# Schematic_EasyEDA_Half_Cat_GSE_Controlle.net
KiCad netlist of a schematic drawn in EasyEDA
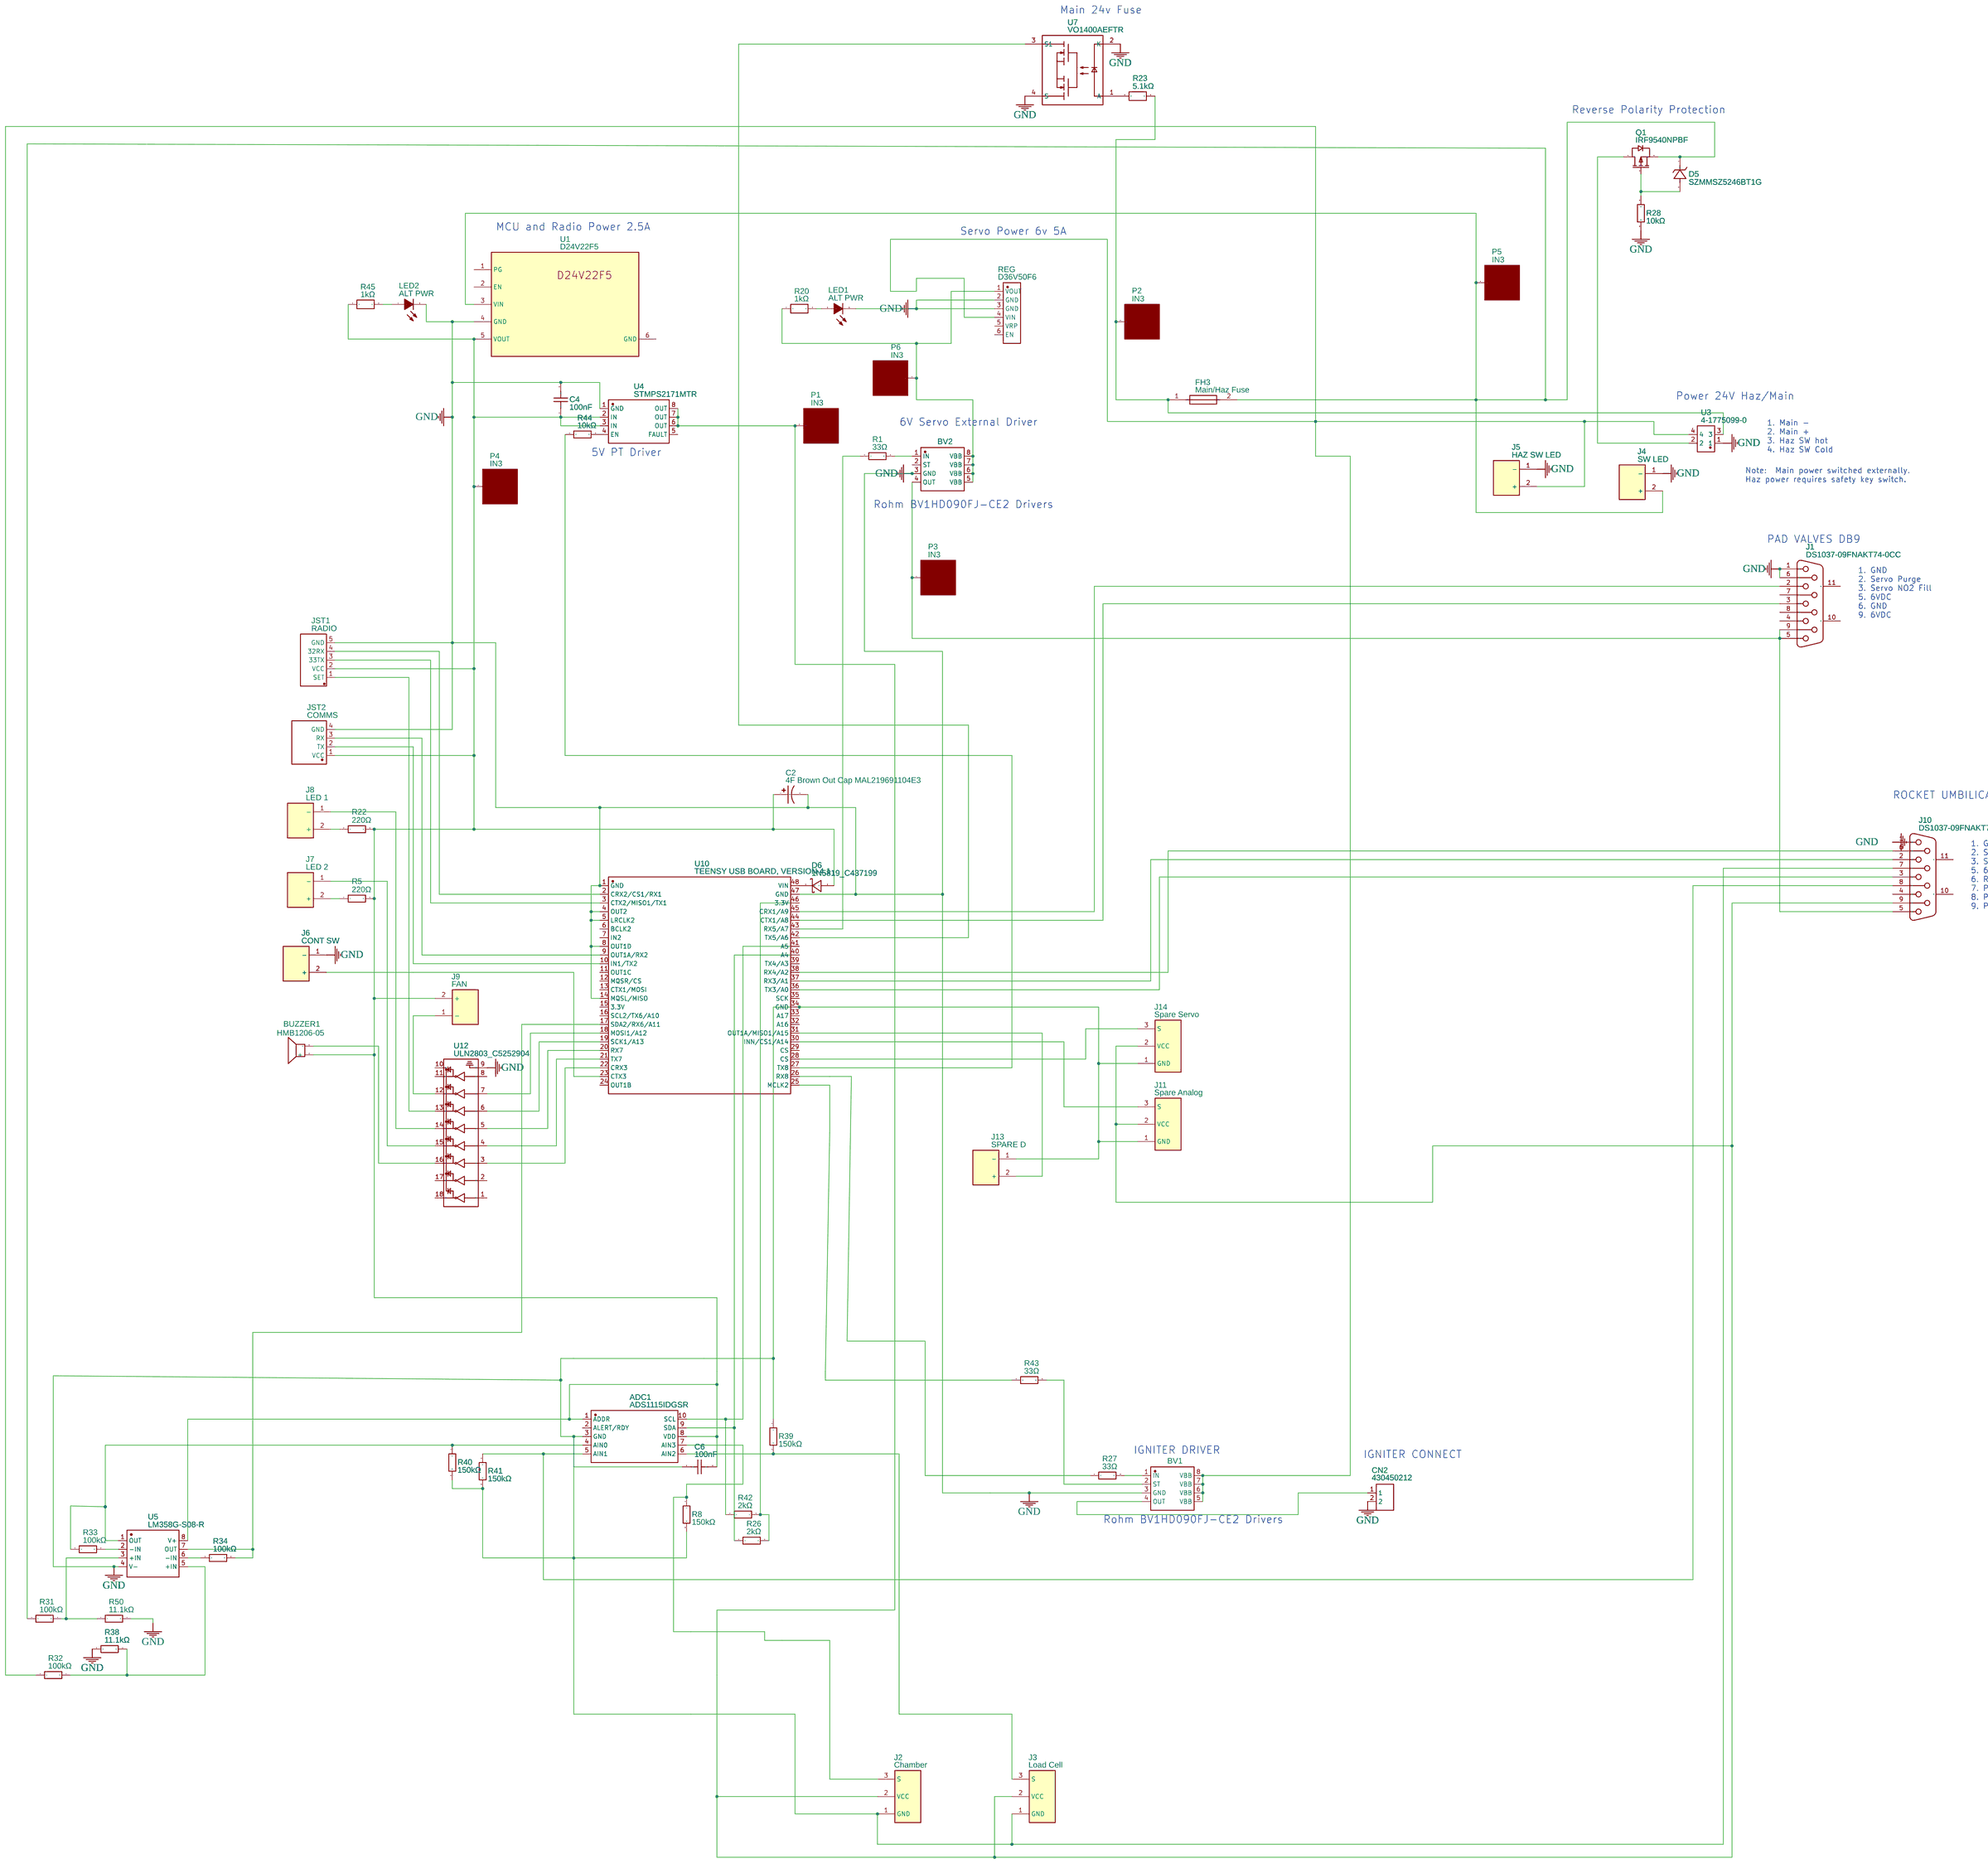
[diagram p0: schematic sheet]

(export (version "E")
  (design (tool "Eeschema 10.0.6"))
  (components
    (comp (ref "ADC1")
      (value "ADS1115IDGSR")
      (fields (field (name "Manufacturer") "TI(德州仪器)"))
      (libsource (lib "") (part "ADS1115IDGSR"))
    )
    (comp (ref "BUZZER1")
      (value "HMB1206-05")
      (fields (field (name "Manufacturer") "HNDZ"))
      (libsource (lib "") (part "HMB1206-05"))
    )
    (comp (ref "BV1")
      (value "BV2")
      (fields (field (name "Manufacturer Part") "BV1HD090FJ-CE2") (field (name "Manufacturer") "ROHM(罗姆)"))
      (libsource (lib "") (part "BV1HD090FJ-CE2"))
    )
    (comp (ref "BV2")
      (value "BV1")
      (fields (field (name "Manufacturer Part") "BV1HD090FJ-CE2") (field (name "Manufacturer") "ROHM(罗姆)"))
      (libsource (lib "") (part "BV1HD090FJ-CE2"))
    )
    (comp (ref "C2") (value "4F Brown Out Cap MAL219691104E3") (libsource (lib "") (part "C_Tan_SMD_A_US")))
    (comp (ref "C4")
      (value "100nF")
      (fields
        (field (name "Manufacturer Part") "GRM155B31C104KA87D")
        (field (name "Manufacturer") "muRata(村田)")
      )
      (libsource (lib "") (part "GRM155B31C104KA87D"))
    )
    (comp (ref "C6")
      (value "100nF")
      (fields
        (field (name "Manufacturer Part") "GRM155B31C104KA87D")
        (field (name "Manufacturer") "muRata(村田)")
      )
      (libsource (lib "") (part "GRM155B31C104KA87D_1"))
    )
    (comp (ref "CN2")
      (value "430450212")
      (fields (field (name "Manufacturer") "MOLEX"))
      (libsource (lib "") (part "430450212"))
    )
    (comp (ref "D5")
      (value "SZMMSZ5246BT1G")
      (fields (field (name "Manufacturer") "onsemi(安森美)"))
      (libsource (lib "") (part "SZMMSZ5246BT1G"))
    )
    (comp (ref "D6")
      (value "1N5819_C437199")
      (fields (field (name "Manufacturer Part") "1N5819") (field (name "Manufacturer") "KEXIN(科信)"))
      (libsource (lib "") (part "1N5819_C437199"))
    )
    (comp (ref "FH3")
      (value "Main/Haz Fuse")
      (fields (field (name "Manufacturer Part") "01000063Z") (field (name "Manufacturer") "Littlefuse"))
      (libsource (lib "") (part "Mini Blade Fuse Holder"))
    )
    (comp (ref "J1")
      (value "DS1037-09FNAKT74-0CC")
      (fields (field (name "Manufacturer") "CONNFLY"))
      (libsource (lib "") (part "DS1037-09FNAKT74-0CC"))
    )
    (comp (ref "J2")
      (value "Chamber")
      (fields (field (name "Manufacturer Part") "B3B-PH-K-S(LF)(SN)") (field (name "Manufacturer") "JST"))
      (libsource (lib "") (part "Unknown_155_680"))
    )
    (comp (ref "J3")
      (value "Load Cell")
      (fields (field (name "Manufacturer Part") "B3B-PH-K-S(LF)(SN)") (field (name "Manufacturer") "JST"))
      (libsource (lib "") (part "Unknown_310_680"))
    )
    (comp (ref "J4")
      (value "SW LED")
      (fields (field (name "Manufacturer Part") "B2B-PH-K-S(LF)(SN)") (field (name "Manufacturer") "JST"))
      (libsource (lib "") (part "B2B-PH-K-S(LF)(SN)"))
    )
    (comp (ref "J5")
      (value "HAZ SW LED")
      (fields (field (name "Manufacturer Part") "B2B-PH-K-S(LF)(SN)") (field (name "Manufacturer") "JST"))
      (libsource (lib "") (part "B2B-PH-K-S(LF)(SN)"))
    )
    (comp (ref "J6")
      (value "CONT SW")
      (fields (field (name "Manufacturer Part") "B2B-PH-K-S(LF)(SN)") (field (name "Manufacturer") "JST"))
      (libsource (lib "") (part "B2B-PH-K-S(LF)(SN)"))
    )
    (comp (ref "J7")
      (value "LED 2")
      (fields (field (name "Manufacturer Part") "B2B-PH-K-S(LF)(SN)") (field (name "Manufacturer") "JST"))
      (libsource (lib "") (part "B2B-PH-K-S(LF)(SN)"))
    )
    (comp (ref "J8")
      (value "LED 1")
      (fields (field (name "Manufacturer Part") "B2B-PH-K-S(LF)(SN)") (field (name "Manufacturer") "JST"))
      (libsource (lib "") (part "B2B-PH-K-S(LF)(SN)"))
    )
    (comp (ref "J9")
      (value "FAN")
      (fields (field (name "Manufacturer Part") "B2B-PH-K-S(LF)(SN)") (field (name "Manufacturer") "JST"))
      (libsource (lib "") (part "B2B-PH-K-S(LF)(SN)_1"))
    )
    (comp (ref "J10")
      (value "DS1037-09FNAKT74-0CC")
      (fields (field (name "Manufacturer") "CONNFLY"))
      (libsource (lib "") (part "DS1037-09FNAKT74-0CC"))
    )
    (comp (ref "J11")
      (value "Spare Analog")
      (fields (field (name "Manufacturer Part") "B3B-PH-K-S(LF)(SN)") (field (name "Manufacturer") "JST"))
      (libsource (lib "") (part "Unknown_455_-95"))
    )
    (comp (ref "J13")
      (value "SPARE D")
      (fields (field (name "Manufacturer Part") "B2B-PH-K-S(LF)(SN)") (field (name "Manufacturer") "JST"))
      (libsource (lib "") (part "B2B-PH-K-S(LF)(SN)"))
    )
    (comp (ref "J14")
      (value "Spare Servo")
      (fields (field (name "Manufacturer Part") "B3B-PH-K-S(LF)(SN)") (field (name "Manufacturer") "JST"))
      (libsource (lib "") (part "Unknown_455_-185"))
    )
    (comp (ref "JST1")
      (value "RADIO")
      (fields (field (name "Manufacturer Part") "B5B-PH-K-S(LF)(SN)") (field (name "Manufacturer") "JST"))
      (libsource (lib "") (part "B5B-PH-K-S-(LF)(SN)"))
    )
    (comp (ref "JST2")
      (value "COMMS")
      (fields (field (name "Manufacturer Part") "B4B-PH-K(LF)(SN)") (field (name "Manufacturer") "JST"))
      (libsource (lib "") (part "B4B-PH-K(LF)(SN)"))
    )
    (comp (ref "LED1")
      (value "ALT PWR")
      (fields
        (field (name "Manufacturer Part") "67-21/R6C-FN2Q1BZ/2T")
        (field (name "Manufacturer") "EVERLIGHT")
      )
      (libsource (lib "") (part "67-21/R6C-FN2Q1BZ/2T"))
    )
    (comp (ref "LED2")
      (value "ALT PWR")
      (fields
        (field (name "Manufacturer Part") "67-21/R6C-FN2Q1BZ/2T")
        (field (name "Manufacturer") "EVERLIGHT")
      )
      (libsource (lib "") (part "67-21/R6C-FN2Q1BZ/2T"))
    )
    (comp (ref "P1")
      (value "IN3")
      (fields (field (name "Manufacturer Part") "Soldering pad"))
      (libsource (lib "") (part "Solder Pad"))
    )
    (comp (ref "P2")
      (value "IN3")
      (fields (field (name "Manufacturer Part") "Soldering pad"))
      (libsource (lib "") (part "Solder Pad"))
    )
    (comp (ref "P3")
      (value "IN3")
      (fields (field (name "Manufacturer Part") "Soldering pad"))
      (libsource (lib "") (part "Solder Pad"))
    )
    (comp (ref "P4")
      (value "IN3")
      (fields (field (name "Manufacturer Part") "Soldering pad"))
      (libsource (lib "") (part "Solder Pad"))
    )
    (comp (ref "P5")
      (value "IN3")
      (fields (field (name "Manufacturer Part") "Soldering pad"))
      (libsource (lib "") (part "Solder Pad"))
    )
    (comp (ref "P6")
      (value "IN3")
      (fields (field (name "Manufacturer Part") "Soldering pad"))
      (libsource (lib "") (part "Solder Pad_1"))
    )
    (comp (ref "Q1")
      (value "IRF9540NPBF")
      (fields (field (name "Manufacturer") "Infineon(英飞凌)"))
      (libsource (lib "") (part "IRF9540NPBF"))
    )
    (comp (ref "R1")
      (value "33Ω")
      (fields (field (name "Manufacturer Part") "RM06FTN33R0") (field (name "Manufacturer") "大毅科技"))
      (libsource (lib "") (part "RM06FTN33R0"))
    )
    (comp (ref "R5")
      (value "220Ω")
      (fields (field (name "Manufacturer Part") "MCWR08X221 JTL") (field (name "Manufacturer") "Multicomp"))
      (libsource (lib "") (part "MCWR08X221-JTL"))
    )
    (comp (ref "R8")
      (value "150kΩ")
      (fields (field (name "Manufacturer Part") "RK73B2ATTD154J") (field (name "Manufacturer") "KOA"))
      (libsource (lib "") (part "RK73B2ATTD154J"))
    )
    (comp (ref "R20")
      (value "1kΩ")
      (fields
        (field (name "Manufacturer Part") "TC0550F1001T5J")
        (field (name "Manufacturer") "UNI-ROYAL(厚声)")
      )
      (libsource (lib "") (part "TC0550F1001T5J"))
    )
    (comp (ref "R22")
      (value "220Ω")
      (fields (field (name "Manufacturer Part") "MCWR08X221 JTL") (field (name "Manufacturer") "Multicomp"))
      (libsource (lib "") (part "MCWR08X221-JTL"))
    )
    (comp (ref "R23")
      (value "5.1kΩ")
      (fields (field (name "Manufacturer Part") "SCR0805F5K1") (field (name "Manufacturer") "VO(翔胜)"))
      (libsource (lib "") (part "SCR0805F5K1"))
    )
    (comp (ref "R26")
      (value "2kΩ")
      (fields (field (name "Manufacturer Part") "RC0805DR-072KL") (field (name "Manufacturer") "YAGEO(国巨)"))
      (libsource (lib "") (part "RC0805DR-072KL"))
    )
    (comp (ref "R27")
      (value "33Ω")
      (fields (field (name "Manufacturer Part") "RM06FTN33R0") (field (name "Manufacturer") "大毅科技"))
      (libsource (lib "") (part "RM06FTN33R0"))
    )
    (comp (ref "R28")
      (value "10kΩ")
      (fields (field (name "Manufacturer Part") "HPCR0805F10K0K9") (field (name "Manufacturer") "RESI(开步睿思)"))
      (libsource (lib "") (part "HPCR0805F10K0K9_1"))
    )
    (comp (ref "R31")
      (value "100kΩ")
      (fields (field (name "Manufacturer Part") "RM10JTN104") (field (name "Manufacturer") "大毅科技"))
      (libsource (lib "") (part "RM10JTN104"))
    )
    (comp (ref "R32")
      (value "100kΩ")
      (fields (field (name "Manufacturer Part") "RM10JTN104") (field (name "Manufacturer") "大毅科技"))
      (libsource (lib "") (part "RM10JTN104"))
    )
    (comp (ref "R33")
      (value "100kΩ")
      (fields (field (name "Manufacturer Part") "RM10JTN104") (field (name "Manufacturer") "大毅科技"))
      (libsource (lib "") (part "RM10JTN104"))
    )
    (comp (ref "R34")
      (value "100kΩ")
      (fields (field (name "Manufacturer Part") "RM10JTN104") (field (name "Manufacturer") "大毅科技"))
      (libsource (lib "") (part "RM10JTN104"))
    )
    (comp (ref "R38")
      (value "11.1kΩ")
      (fields (field (name "Manufacturer Part") "RT0603BRD0711K1L") (field (name "Manufacturer") "YAGEO(国巨)"))
      (libsource (lib "") (part "RT0603BRD0711K1L"))
    )
    (comp (ref "R39")
      (value "150kΩ")
      (fields (field (name "Manufacturer Part") "RK73B2ATTD154J") (field (name "Manufacturer") "KOA"))
      (libsource (lib "") (part "RK73B2ATTD154J"))
    )
    (comp (ref "R40")
      (value "150kΩ")
      (fields (field (name "Manufacturer Part") "RK73B2ATTD154J") (field (name "Manufacturer") "KOA"))
      (libsource (lib "") (part "RK73B2ATTD154J"))
    )
    (comp (ref "R41")
      (value "150kΩ")
      (fields (field (name "Manufacturer Part") "RK73B2ATTD154J") (field (name "Manufacturer") "KOA"))
      (libsource (lib "") (part "RK73B2ATTD154J"))
    )
    (comp (ref "R42")
      (value "2kΩ")
      (fields (field (name "Manufacturer Part") "RC0805DR-072KL") (field (name "Manufacturer") "YAGEO(国巨)"))
      (libsource (lib "") (part "RC0805DR-072KL"))
    )
    (comp (ref "R43")
      (value "33Ω")
      (fields (field (name "Manufacturer Part") "RM06FTN33R0") (field (name "Manufacturer") "大毅科技"))
      (libsource (lib "") (part "RM06FTN33R0"))
    )
    (comp (ref "R44")
      (value "10kΩ")
      (fields (field (name "Manufacturer Part") "HPCR0805F10K0K9") (field (name "Manufacturer") "RESI(开步睿思)"))
      (libsource (lib "") (part "HPCR0805F10K0K9"))
    )
    (comp (ref "R45")
      (value "1kΩ")
      (fields
        (field (name "Manufacturer Part") "TC0550F1001T5J")
        (field (name "Manufacturer") "UNI-ROYAL(厚声)")
      )
      (libsource (lib "") (part "TC0550F1001T5J"))
    )
    (comp (ref "R50")
      (value "11.1kΩ")
      (fields (field (name "Manufacturer Part") "RT0603BRD0711K1L") (field (name "Manufacturer") "YAGEO(国巨)"))
      (libsource (lib "") (part "RT0603BRD0711K1L"))
    )
    (comp (ref "REG") (value "D36V50F6") (libsource (lib "") (part "D36V50F6")))
    (comp (ref "U1") (value "D24V22F5") (libsource (lib "") (part "D24V22F5")))
    (comp (ref "U3")
      (value "4-1775099-0")
      (fields (field (name "Manufacturer") "TE Connectivity(美国泰科)"))
      (libsource (lib "") (part "4-1775099-0"))
    )
    (comp (ref "U4")
      (value "STMPS2171MTR")
      (fields (field (name "Manufacturer") "ST(意法半导体)"))
      (libsource (lib "") (part "STMPS2171MTR"))
    )
    (comp (ref "U5")
      (value "LM358G-S08-R")
      (fields (field (name "Manufacturer") "UTC"))
      (libsource (lib "") (part "LM358G-S08-R"))
    )
    (comp (ref "U7")
      (value "VO1400AEFTR")
      (fields (field (name "Manufacturer") "VISHAY(威世)"))
      (libsource (lib "") (part "VO1400AEFTR"))
    )
    (comp (ref "U10")
      (value "TEENSY USB BOARD, VERSION 4.1")
      (fields (field (name "Manufacturer Part") "Teensy USB Board, Version 4.1"))
      (libsource (lib "") (part "TEENSY USB BOARD, VERSION 4.1"))
    )
    (comp (ref "U12")
      (value "ULN2803_C5252904")
      (fields (field (name "Manufacturer Part") "ULN2803") (field (name "Manufacturer") "MSKSEMI(美森科)"))
      (libsource (lib "") (part "ULN2803_C5252904"))
    )
  )
  (nets
    (net (code "1") (name "GND") (class "Default")
      (node (ref "ADC1") (pin "3") (pinfunction "GND_3") (pintype "unspecified"))
      (node (ref "BV1") (pin "3") (pinfunction "GND_3") (pintype "unspecified"))
      (node (ref "BV2") (pin "3") (pinfunction "GND_3") (pintype "unspecified"))
      (node (ref "C2") (pin "2") (pinfunction "2_2") (pintype "unspecified"))
      (node (ref "C4") (pin "2") (pinfunction "2_2") (pintype "unspecified"))
      (node (ref "C6") (pin "1") (pinfunction "1_1") (pintype "unspecified"))
      (node (ref "CN2") (pin "2") (pinfunction "2_2") (pintype "unspecified"))
      (node (ref "J1") (pin "1") (pinfunction "1_1") (pintype "input"))
      (node (ref "J1") (pin "6") (pinfunction "6_6") (pintype "input"))
      (node (ref "J10") (pin "1") (pinfunction "1_1") (pintype "input"))
      (node (ref "J10") (pin "7") (pinfunction "7_7") (pintype "input"))
      (node (ref "J11") (pin "1") (pinfunction "GND_1") (pintype "input"))
      (node (ref "J13") (pin "1") (pinfunction "-_1") (pintype "input"))
      (node (ref "J14") (pin "1") (pinfunction "GND_1") (pintype "input"))
      (node (ref "J2") (pin "1") (pinfunction "GND_1") (pintype "input"))
      (node (ref "J3") (pin "1") (pinfunction "GND_1") (pintype "input"))
      (node (ref "J4") (pin "1") (pinfunction "-_1") (pintype "input"))
      (node (ref "J5") (pin "1") (pinfunction "-_1") (pintype "input"))
      (node (ref "J6") (pin "1") (pinfunction "-_1") (pintype "input"))
      (node (ref "JST1") (pin "5") (pinfunction "GND_5") (pintype "unspecified"))
      (node (ref "JST2") (pin "4") (pinfunction "GND_4") (pintype "unspecified"))
      (node (ref "LED1") (pin "2") (pinfunction "C_2") (pintype "input"))
      (node (ref "LED2") (pin "2") (pinfunction "C_2") (pintype "input"))
      (node (ref "R28") (pin "2") (pinfunction "2_2") (pintype "unspecified"))
      (node (ref "R38") (pin "1") (pinfunction "1_1") (pintype "unspecified"))
      (node (ref "R39") (pin "1") (pinfunction "1_1") (pintype "unspecified"))
      (node (ref "R40") (pin "2") (pinfunction "2_2") (pintype "unspecified"))
      (node (ref "R41") (pin "2") (pinfunction "2_2") (pintype "unspecified"))
      (node (ref "R50") (pin "2") (pinfunction "2_2") (pintype "unspecified"))
      (node (ref "R8") (pin "2") (pinfunction "2_2") (pintype "unspecified"))
      (node (ref "REG") (pin "2") (pinfunction "GND_2") (pintype "unspecified"))
      (node (ref "REG") (pin "3") (pinfunction "GND_3") (pintype "unspecified"))
      (node (ref "U1") (pin "4") (pinfunction "GND_4") (pintype "unspecified"))
      (node (ref "U10") (pin "1") (pinfunction "GND_1") (pintype "unspecified"))
      (node (ref "U10") (pin "14") (pinfunction "MQSL/MISO_14") (pintype "unspecified"))
      (node (ref "U10") (pin "34") (pinfunction "GND_34") (pintype "unspecified"))
      (node (ref "U10") (pin "4") (pinfunction "OUT2_4") (pintype "unspecified"))
      (node (ref "U10") (pin "47") (pinfunction "GND_47") (pintype "unspecified"))
      (node (ref "U10") (pin "5") (pinfunction "LRCLK2_5") (pintype "unspecified"))
      (node (ref "U10") (pin "8") (pinfunction "OUT1D_8") (pintype "unspecified"))
      (node (ref "U12") (pin "9") (pinfunction "GND_9") (pintype "unspecified"))
      (node (ref "U3") (pin "1") (pinfunction "1_1") (pintype "unspecified"))
      (node (ref "U4") (pin "1") (pinfunction "GND_1") (pintype "unspecified"))
      (node (ref "U5") (pin "4") (pinfunction "V-_4") (pintype "unspecified"))
      (node (ref "U7") (pin "2") (pinfunction "K_2") (pintype "unspecified"))
      (node (ref "U7") (pin "4") (pinfunction "S_4") (pintype "unspecified"))
    )
    (net (code "2") (name "Net-(ADC1-ADDR)") (class "Default")
      (node (ref "ADC1") (pin "1") (pinfunction "ADDR_1") (pintype "unspecified"))
      (node (ref "ADC1") (pin "8") (pinfunction "VDD_8") (pintype "unspecified"))
      (node (ref "BUZZER1") (pin "1") (pinfunction "+_1") (pintype "unspecified"))
      (node (ref "C2") (pin "1") (pinfunction "1_1") (pintype "unspecified"))
      (node (ref "C4") (pin "1") (pinfunction "1_1") (pintype "unspecified"))
      (node (ref "C6") (pin "2") (pinfunction "2_2") (pintype "unspecified"))
      (node (ref "D6") (pin "2") (pinfunction "A_2") (pintype "unspecified"))
      (node (ref "J9") (pin "2") (pinfunction "+_2") (pintype "input"))
      (node (ref "JST1") (pin "2") (pinfunction "VCC_2") (pintype "unspecified"))
      (node (ref "JST2") (pin "1") (pinfunction "VCC_1") (pintype "unspecified"))
      (node (ref "P4") (pin "1") (pinfunction "1_1") (pintype "unspecified"))
      (node (ref "R22") (pin "2") (pinfunction "2_2") (pintype "unspecified"))
      (node (ref "R45") (pin "1") (pinfunction "1_1") (pintype "unspecified"))
      (node (ref "R5") (pin "2") (pinfunction "2_2") (pintype "unspecified"))
      (node (ref "U1") (pin "5") (pinfunction "VOUT_5") (pintype "unspecified"))
      (node (ref "U4") (pin "2") (pinfunction "IN_2") (pintype "unspecified"))
      (node (ref "U4") (pin "3") (pinfunction "IN_3") (pintype "unspecified"))
      (node (ref "U5") (pin "8") (pinfunction "V+_8") (pintype "unspecified"))
    )
    (net (code "3") (name "Net-(ADC1-AIN0)") (class "Default")
      (node (ref "ADC1") (pin "4") (pinfunction "AIN0_4") (pintype "unspecified"))
      (node (ref "R33") (pin "1") (pinfunction "1_1") (pintype "input"))
      (node (ref "R40") (pin "1") (pinfunction "1_1") (pintype "unspecified"))
      (node (ref "U5") (pin "1") (pinfunction "OUT_1") (pintype "unspecified"))
    )
    (net (code "4") (name "Net-(ADC1-AIN1)") (class "Default")
      (node (ref "ADC1") (pin "5") (pinfunction "AIN1_5") (pintype "unspecified"))
      (node (ref "J10") (pin "8") (pinfunction "8_8") (pintype "input"))
      (node (ref "R41") (pin "1") (pinfunction "1_1") (pintype "unspecified"))
    )
    (net (code "5") (name "Net-(ADC1-AIN2)") (class "Default")
      (node (ref "ADC1") (pin "6") (pinfunction "AIN2_6") (pintype "unspecified"))
      (node (ref "J3") (pin "3") (pinfunction "S_3") (pintype "input"))
      (node (ref "R39") (pin "2") (pinfunction "2_2") (pintype "unspecified"))
    )
    (net (code "6") (name "Net-(ADC1-AIN3)") (class "Default")
      (node (ref "ADC1") (pin "7") (pinfunction "AIN3_7") (pintype "unspecified"))
      (node (ref "J2") (pin "3") (pinfunction "S_3") (pintype "input"))
      (node (ref "R8") (pin "1") (pinfunction "1_1") (pintype "unspecified"))
    )
    (net (code "7") (name "Net-(ADC1-SCL)") (class "Default")
      (node (ref "ADC1") (pin "10") (pinfunction "SCL_10") (pintype "unspecified"))
      (node (ref "R42") (pin "1") (pinfunction "1_1") (pintype "unspecified"))
      (node (ref "U10") (pin "41") (pinfunction "A5_41") (pintype "unspecified"))
    )
    (net (code "8") (name "Net-(ADC1-SDA)") (class "Default")
      (node (ref "ADC1") (pin "9") (pinfunction "SDA_9") (pintype "unspecified"))
      (node (ref "R26") (pin "1") (pinfunction "1_1") (pintype "unspecified"))
      (node (ref "U10") (pin "40") (pinfunction "A4_40") (pintype "unspecified"))
    )
    (net (code "9") (name "Net-(BV1-IN)") (class "Default")
      (node (ref "BV1") (pin "1") (pinfunction "IN_1") (pintype "unspecified"))
      (node (ref "R1") (pin "2") (pinfunction "2_2") (pintype "unspecified"))
    )
    (net (code "10") (name "Net-(BV1-OUT)") (class "Default")
      (node (ref "BV1") (pin "4") (pinfunction "OUT_4") (pintype "unspecified"))
      (node (ref "J1") (pin "5") (pinfunction "5_5") (pintype "input"))
      (node (ref "J1") (pin "9") (pinfunction "9_9") (pintype "input"))
      (node (ref "J10") (pin "5") (pinfunction "5_5") (pintype "input"))
      (node (ref "P3") (pin "1") (pinfunction "1_1") (pintype "unspecified"))
    )
    (net (code "11") (name "Net-(BV2-IN)") (class "Default")
      (node (ref "BV2") (pin "1") (pinfunction "IN_1") (pintype "unspecified"))
      (node (ref "R27") (pin "2") (pinfunction "2_2") (pintype "unspecified"))
    )
    (net (code "12") (name "Net-(BV2-OUT)") (class "Default")
      (node (ref "BV2") (pin "4") (pinfunction "OUT_4") (pintype "unspecified"))
      (node (ref "CN2") (pin "1") (pinfunction "1_1") (pintype "unspecified"))
    )
    (net (code "13") (name "Net-(BV2-ST)") (class "Default")
      (node (ref "BV2") (pin "2") (pinfunction "ST_2") (pintype "unspecified"))
      (node (ref "R43") (pin "2") (pinfunction "2_2") (pintype "unspecified"))
    )
    (net (code "14") (name "Net-(D5-A)") (class "Default")
      (node (ref "D5") (pin "2") (pinfunction "A_2") (pintype "unspecified"))
      (node (ref "Q1") (pin "1") (pinfunction "G_1") (pintype "unspecified"))
      (node (ref "R28") (pin "1") (pinfunction "1_1") (pintype "unspecified"))
    )
    (net (code "15") (name "Net-(D5-C)") (class "Default")
      (node (ref "D5") (pin "1") (pinfunction "C_1") (pintype "unspecified"))
      (node (ref "FH3") (pin "2") (pinfunction "2_2") (pintype "unspecified"))
      (node (ref "J4") (pin "2") (pinfunction "+_2") (pintype "input"))
      (node (ref "P5") (pin "1") (pinfunction "1_1") (pintype "unspecified"))
      (node (ref "Q1") (pin "3") (pinfunction "S_3") (pintype "unspecified"))
      (node (ref "R31") (pin "1") (pinfunction "1_1") (pintype "input"))
      (node (ref "U1") (pin "3") (pinfunction "VIN_3") (pintype "unspecified"))
    )
    (net (code "16") (name "Net-(D6-C)") (class "Default")
      (node (ref "D6") (pin "1") (pinfunction "C_1") (pintype "unspecified"))
      (node (ref "U10") (pin "48") (pinfunction "VIN_48") (pintype "unspecified"))
    )
    (net (code "17") (name "Net-(FH3-Pad1)") (class "Default")
      (node (ref "FH3") (pin "1") (pinfunction "1_1") (pintype "unspecified"))
      (node (ref "P2") (pin "1") (pinfunction "1_1") (pintype "unspecified"))
      (node (ref "R23") (pin "2") (pinfunction "2_2") (pintype "unspecified"))
      (node (ref "U3") (pin "3") (pinfunction "3_3") (pintype "unspecified"))
    )
    (net (code "18") (name "Net-(J5-+)") (class "Default")
      (node (ref "BV2") (pin "5") (pinfunction "VBB_5") (pintype "unspecified"))
      (node (ref "BV2") (pin "6") (pinfunction "VBB_6") (pintype "unspecified"))
      (node (ref "BV2") (pin "7") (pinfunction "VBB_7") (pintype "unspecified"))
      (node (ref "BV2") (pin "8") (pinfunction "VBB_8") (pintype "unspecified"))
      (node (ref "J5") (pin "2") (pinfunction "+_2") (pintype "input"))
      (node (ref "R32") (pin "1") (pinfunction "1_1") (pintype "input"))
      (node (ref "REG") (pin "4") (pinfunction "VIN_4") (pintype "unspecified"))
      (node (ref "U3") (pin "4") (pinfunction "4_4") (pintype "unspecified"))
    )
    (net (code "19") (name "Net-(J6-+)") (class "Default")
      (node (ref "J6") (pin "2") (pinfunction "+_2") (pintype "input"))
      (node (ref "U10") (pin "23") (pinfunction "CTX3_23") (pintype "unspecified"))
    )
    (net (code "20") (name "Net-(J7-+)") (class "Default")
      (node (ref "J7") (pin "2") (pinfunction "+_2") (pintype "input"))
      (node (ref "R5") (pin "1") (pinfunction "1_1") (pintype "unspecified"))
    )
    (net (code "21") (name "Net-(J7--)") (class "Default")
      (node (ref "J7") (pin "1") (pinfunction "-_1") (pintype "input"))
      (node (ref "U12") (pin "15") (pinfunction "4OUT_15") (pintype "unspecified"))
    )
    (net (code "22") (name "Net-(J8-+)") (class "Default")
      (node (ref "J8") (pin "2") (pinfunction "+_2") (pintype "input"))
      (node (ref "R22") (pin "1") (pinfunction "1_1") (pintype "unspecified"))
    )
    (net (code "23") (name "Net-(J8--)") (class "Default")
      (node (ref "J8") (pin "1") (pinfunction "-_1") (pintype "input"))
      (node (ref "U12") (pin "14") (pinfunction "5OUT_14") (pintype "unspecified"))
    )
    (net (code "24") (name "Net-(J9--)") (class "Default")
      (node (ref "J9") (pin "1") (pinfunction "-_1") (pintype "input"))
      (node (ref "U12") (pin "12") (pinfunction "7OUT_12") (pintype "unspecified"))
    )
    (net (code "25") (name "Net-(J11-S)") (class "Default")
      (node (ref "J11") (pin "3") (pinfunction "S_3") (pintype "input"))
      (node (ref "U10") (pin "30") (pinfunction "INN/CS1/A14_30") (pintype "unspecified"))
    )
    (net (code "26") (name "Net-(J11-VCC)") (class "Default")
      (node (ref "J10") (pin "9") (pinfunction "9_9") (pintype "input"))
      (node (ref "J11") (pin "2") (pinfunction "VCC_2") (pintype "input"))
      (node (ref "J14") (pin "2") (pinfunction "VCC_2") (pintype "input"))
      (node (ref "J2") (pin "2") (pinfunction "VCC_2") (pintype "input"))
      (node (ref "J3") (pin "2") (pinfunction "VCC_2") (pintype "input"))
      (node (ref "P1") (pin "1") (pinfunction "1_1") (pintype "unspecified"))
      (node (ref "U4") (pin "6") (pinfunction "OUT_6") (pintype "unspecified"))
      (node (ref "U4") (pin "7") (pinfunction "OUT_7") (pintype "unspecified"))
      (node (ref "U4") (pin "8") (pinfunction "OUT_8") (pintype "unspecified"))
    )
    (net (code "27") (name "Net-(J13-+)") (class "Default")
      (node (ref "J13") (pin "2") (pinfunction "+_2") (pintype "input"))
      (node (ref "U10") (pin "31") (pinfunction "OUT1A/MISO1/A15_31") (pintype "unspecified"))
    )
    (net (code "28") (name "Net-(J14-S)") (class "Default")
      (node (ref "J14") (pin "3") (pinfunction "S_3") (pintype "input"))
      (node (ref "U10") (pin "28") (pinfunction "CS_28") (pintype "unspecified"))
    )
    (net (code "29") (name "Net-(JST1-32RX)") (class "Default")
      (node (ref "JST1") (pin "4") (pinfunction "32RX_4") (pintype "unspecified"))
      (node (ref "U10") (pin "2") (pinfunction "CRX2/CS1/RX1_2") (pintype "unspecified"))
    )
    (net (code "30") (name "Net-(JST1-33TX)") (class "Default")
      (node (ref "JST1") (pin "3") (pinfunction "33TX_3") (pintype "unspecified"))
      (node (ref "U10") (pin "3") (pinfunction "CTX2/MISO1/TX1_3") (pintype "unspecified"))
    )
    (net (code "31") (name "Net-(JST1-SET)") (class "Default")
      (node (ref "JST1") (pin "1") (pinfunction "SET_1") (pintype "unspecified"))
      (node (ref "U12") (pin "13") (pinfunction "6OUT_13") (pintype "unspecified"))
    )
    (net (code "32") (name "Net-(JST2-RX)") (class "Default")
      (node (ref "JST2") (pin "3") (pinfunction "RX_3") (pintype "unspecified"))
      (node (ref "U10") (pin "9") (pinfunction "OUT1A/RX2_9") (pintype "unspecified"))
    )
    (net (code "33") (name "Net-(JST2-TX)") (class "Default")
      (node (ref "JST2") (pin "2") (pinfunction "TX_2") (pintype "unspecified"))
      (node (ref "U10") (pin "10") (pinfunction "IN1/TX2_10") (pintype "unspecified"))
    )
    (net (code "34") (name "Net-(LED1-A)") (class "Default")
      (node (ref "LED1") (pin "1") (pinfunction "A_1") (pintype "input"))
      (node (ref "R20") (pin "2") (pinfunction "2_2") (pintype "unspecified"))
    )
    (net (code "35") (name "Net-(LED2-A)") (class "Default")
      (node (ref "LED2") (pin "1") (pinfunction "A_1") (pintype "input"))
      (node (ref "R45") (pin "2") (pinfunction "2_2") (pintype "unspecified"))
    )
    (net (code "36") (name "Net-(Q1-D)") (class "Default")
      (node (ref "Q1") (pin "2") (pinfunction "D_2") (pintype "unspecified"))
      (node (ref "U3") (pin "2") (pinfunction "2_2") (pintype "unspecified"))
    )
    (net (code "37") (name "Net-(R26-Pad2)") (class "Default")
      (node (ref "R26") (pin "2") (pinfunction "2_2") (pintype "unspecified"))
      (node (ref "R42") (pin "2") (pinfunction "2_2") (pintype "unspecified"))
      (node (ref "U10") (pin "46") (pinfunction "3.3V_46") (pintype "unspecified"))
    )
    (net (code "38") (name "Net-(R31-Pad2)") (class "Default")
      (node (ref "R31") (pin "2") (pinfunction "2_2") (pintype "input"))
      (node (ref "R50") (pin "1") (pinfunction "1_1") (pintype "unspecified"))
      (node (ref "U5") (pin "3") (pinfunction "+IN_3") (pintype "unspecified"))
    )
    (net (code "39") (name "Net-(R32-Pad2)") (class "Default")
      (node (ref "R32") (pin "2") (pinfunction "2_2") (pintype "input"))
      (node (ref "R38") (pin "2") (pinfunction "2_2") (pintype "unspecified"))
      (node (ref "U5") (pin "5") (pinfunction "+IN_5") (pintype "unspecified"))
    )
    (net (code "40") (name "Net-(R33-Pad2)") (class "Default")
      (node (ref "R33") (pin "2") (pinfunction "2_2") (pintype "input"))
      (node (ref "U5") (pin "2") (pinfunction "-IN_2") (pintype "unspecified"))
    )
    (net (code "41") (name "Net-(R34-Pad1)") (class "Default")
      (node (ref "R34") (pin "1") (pinfunction "1_1") (pintype "input"))
      (node (ref "U5") (pin "6") (pinfunction "-IN_6") (pintype "unspecified"))
    )
    (net (code "42") (name "Net-(REG-VOUT)") (class "Default")
      (node (ref "BV1") (pin "5") (pinfunction "VBB_5") (pintype "unspecified"))
      (node (ref "BV1") (pin "6") (pinfunction "VBB_6") (pintype "unspecified"))
      (node (ref "BV1") (pin "7") (pinfunction "VBB_7") (pintype "unspecified"))
      (node (ref "BV1") (pin "8") (pinfunction "VBB_8") (pintype "unspecified"))
      (node (ref "P6") (pin "1") (pinfunction "1_1") (pintype "unspecified"))
      (node (ref "R20") (pin "1") (pinfunction "1_1") (pintype "unspecified"))
      (node (ref "REG") (pin "1") (pinfunction "VOUT_1") (pintype "unspecified"))
    )
    (net (code "43") (name "Net-(U4-EN)") (class "Default")
      (node (ref "R44") (pin "2") (pinfunction "2_2") (pintype "unspecified"))
      (node (ref "U4") (pin "4") (pinfunction "EN_4") (pintype "unspecified"))
    )
    (net (code "44") (name "Net-(U7-A)") (class "Default")
      (node (ref "R23") (pin "1") (pinfunction "1_1") (pintype "unspecified"))
      (node (ref "U7") (pin "1") (pinfunction "A_1") (pintype "unspecified"))
    )
    (net (code "45") (name "Net-(U10-CRX1{slash}A9)") (class "Default")
      (node (ref "J1") (pin "2") (pinfunction "2_2") (pintype "input"))
      (node (ref "U10") (pin "45") (pinfunction "CRX1/A9_45") (pintype "unspecified"))
    )
    (net (code "46") (name "Net-(U10-CRX3)") (class "Default")
      (node (ref "U10") (pin "22") (pinfunction "CRX3_22") (pintype "unspecified"))
      (node (ref "U12") (pin "3") (pinfunction "3IN_3") (pintype "unspecified"))
    )
    (net (code "47") (name "Net-(U10-CTX1{slash}A8)") (class "Default")
      (node (ref "J1") (pin "3") (pinfunction "3_3") (pintype "input"))
      (node (ref "U10") (pin "44") (pinfunction "CTX1/A8_44") (pintype "unspecified"))
    )
    (net (code "48") (name "Net-(U10-MCLK2)") (class "Default")
      (node (ref "R43") (pin "1") (pinfunction "1_1") (pintype "unspecified"))
      (node (ref "U10") (pin "25") (pinfunction "MCLK2_25") (pintype "unspecified"))
    )
    (net (code "49") (name "Net-(U10-MOSI1{slash}A12)") (class "Default")
      (node (ref "U10") (pin "18") (pinfunction "MOSI1/A12_18") (pintype "unspecified"))
      (node (ref "U12") (pin "7") (pinfunction "7IN_7") (pintype "unspecified"))
    )
    (net (code "50") (name "Net-(U10-RX3{slash}A1)") (class "Default")
      (node (ref "J10") (pin "2") (pinfunction "2_2") (pintype "input"))
      (node (ref "U10") (pin "37") (pinfunction "RX3/A1_37") (pintype "unspecified"))
    )
    (net (code "51") (name "Net-(U10-RX4{slash}A2)") (class "Default")
      (node (ref "J10") (pin "6") (pinfunction "6_6") (pintype "input"))
      (node (ref "U10") (pin "38") (pinfunction "RX4/A2_38") (pintype "unspecified"))
    )
    (net (code "52") (name "Net-(U10-RX5{slash}A7)") (class "Default")
      (node (ref "R1") (pin "1") (pinfunction "1_1") (pintype "unspecified"))
      (node (ref "U10") (pin "43") (pinfunction "RX5/A7_43") (pintype "unspecified"))
    )
    (net (code "53") (name "Net-(U10-RX7)") (class "Default")
      (node (ref "U10") (pin "20") (pinfunction "RX7_20") (pintype "unspecified"))
      (node (ref "U12") (pin "5") (pinfunction "5IN_5") (pintype "unspecified"))
    )
    (net (code "54") (name "Net-(U10-RX8)") (class "Default")
      (node (ref "R27") (pin "1") (pinfunction "1_1") (pintype "unspecified"))
      (node (ref "U10") (pin "26") (pinfunction "RX8_26") (pintype "unspecified"))
    )
    (net (code "55") (name "Net-(U10-SCK1{slash}A13)") (class "Default")
      (node (ref "U10") (pin "19") (pinfunction "SCK1/A13_19") (pintype "unspecified"))
      (node (ref "U12") (pin "6") (pinfunction "6IN_6") (pintype "unspecified"))
    )
    (net (code "56") (name "Net-(U10-SDA2{slash}RX6{slash}A11)") (class "Default")
      (node (ref "R34") (pin "2") (pinfunction "2_2") (pintype "input"))
      (node (ref "U10") (pin "17") (pinfunction "SDA2/RX6/A11_17") (pintype "unspecified"))
      (node (ref "U5") (pin "7") (pinfunction "OUT_7") (pintype "unspecified"))
    )
    (net (code "57") (name "Net-(U10-TX3{slash}A0)") (class "Default")
      (node (ref "J10") (pin "3") (pinfunction "3_3") (pintype "input"))
      (node (ref "U10") (pin "36") (pinfunction "TX3/A0_36") (pintype "unspecified"))
    )
    (net (code "58") (name "Net-(U10-TX5{slash}A6)") (class "Default")
      (node (ref "U10") (pin "42") (pinfunction "TX5/A6_42") (pintype "unspecified"))
      (node (ref "U7") (pin "3") (pinfunction "S1_3") (pintype "unspecified"))
    )
    (net (code "59") (name "Net-(U10-TX7)") (class "Default")
      (node (ref "U10") (pin "21") (pinfunction "TX7_21") (pintype "unspecified"))
      (node (ref "U12") (pin "4") (pinfunction "4IN_4") (pintype "unspecified"))
    )
    (net (code "60") (name "Net-(U10-TX8)") (class "Default")
      (node (ref "R44") (pin "1") (pinfunction "1_1") (pintype "unspecified"))
      (node (ref "U10") (pin "27") (pinfunction "TX8_27") (pintype "unspecified"))
    )
    (net (code "61") (name "Net-(U12-3OUT)") (class "Default")
      (node (ref "BUZZER1") (pin "2") (pinfunction "2_2") (pintype "unspecified"))
      (node (ref "U12") (pin "16") (pinfunction "3OUT_16") (pintype "unspecified"))
    )
    (net (code "62") (name "unconnected-(ADC1-ALERT{slash}RDY-Pad2)") (class "Default")
      (node (ref "ADC1") (pin "2") (pinfunction "ALERT/RDY_2") (pintype "unspecified"))
    )
    (net (code "63") (name "unconnected-(BV1-ST-Pad2)") (class "Default")
      (node (ref "BV1") (pin "2") (pinfunction "ST_2") (pintype "unspecified"))
    )
    (net (code "64") (name "unconnected-(J1-MH1-Pad10)") (class "Default")
      (node (ref "J1") (pin "10") (pinfunction "MH1_10") (pintype "input"))
    )
    (net (code "65") (name "unconnected-(J1-MH2-Pad11)") (class "Default")
      (node (ref "J1") (pin "11") (pinfunction "MH2_11") (pintype "input"))
    )
    (net (code "66") (name "unconnected-(J1-Pad4)") (class "Default")
      (node (ref "J1") (pin "4") (pinfunction "4_4") (pintype "input"))
    )
    (net (code "67") (name "unconnected-(J1-Pad7)") (class "Default")
      (node (ref "J1") (pin "7") (pinfunction "7_7") (pintype "input"))
    )
    (net (code "68") (name "unconnected-(J1-Pad8)") (class "Default")
      (node (ref "J1") (pin "8") (pinfunction "8_8") (pintype "input"))
    )
    (net (code "69") (name "unconnected-(J10-MH1-Pad10)") (class "Default")
      (node (ref "J10") (pin "10") (pinfunction "MH1_10") (pintype "input"))
    )
    (net (code "70") (name "unconnected-(J10-MH2-Pad11)") (class "Default")
      (node (ref "J10") (pin "11") (pinfunction "MH2_11") (pintype "input"))
    )
    (net (code "71") (name "unconnected-(J10-Pad4)") (class "Default")
      (node (ref "J10") (pin "4") (pinfunction "4_4") (pintype "input"))
    )
    (net (code "72") (name "unconnected-(REG-EN-Pad6)") (class "Default")
      (node (ref "REG") (pin "6") (pinfunction "EN_6") (pintype "unspecified"))
    )
    (net (code "73") (name "unconnected-(REG-VRP-Pad5)") (class "Default")
      (node (ref "REG") (pin "5") (pinfunction "VRP_5") (pintype "unspecified"))
    )
    (net (code "74") (name "unconnected-(U1-EN-Pad2)") (class "Default")
      (node (ref "U1") (pin "2") (pinfunction "EN_2") (pintype "unspecified"))
    )
    (net (code "75") (name "unconnected-(U1-GND-Pad6)") (class "Default")
      (node (ref "U1") (pin "6") (pinfunction "GND_6") (pintype "unspecified"))
    )
    (net (code "76") (name "unconnected-(U1-PG-Pad1)") (class "Default")
      (node (ref "U1") (pin "1") (pinfunction "PG_1") (pintype "unspecified"))
    )
    (net (code "77") (name "unconnected-(U4-FAULT-Pad5)") (class "Default")
      (node (ref "U4") (pin "5") (pinfunction "FAULT_5") (pintype "unspecified"))
    )
    (net (code "78") (name "unconnected-(U10-3.3V-Pad15)") (class "Default")
      (node (ref "U10") (pin "15") (pinfunction "3.3V_15") (pintype "unspecified"))
    )
    (net (code "79") (name "unconnected-(U10-A16-Pad32)") (class "Default")
      (node (ref "U10") (pin "32") (pinfunction "A16_32") (pintype "unspecified"))
    )
    (net (code "80") (name "unconnected-(U10-A17-Pad33)") (class "Default")
      (node (ref "U10") (pin "33") (pinfunction "A17_33") (pintype "unspecified"))
    )
    (net (code "81") (name "unconnected-(U10-BCLK2-Pad6)") (class "Default")
      (node (ref "U10") (pin "6") (pinfunction "BCLK2_6") (pintype "unspecified"))
    )
    (net (code "82") (name "unconnected-(U10-CS-Pad29)") (class "Default")
      (node (ref "U10") (pin "29") (pinfunction "CS_29") (pintype "unspecified"))
    )
    (net (code "83") (name "unconnected-(U10-CTX1{slash}MOSI-Pad13)") (class "Default")
      (node (ref "U10") (pin "13") (pinfunction "CTX1/MOSI_13") (pintype "unspecified"))
    )
    (net (code "84") (name "unconnected-(U10-IN2-Pad7)") (class "Default")
      (node (ref "U10") (pin "7") (pinfunction "IN2_7") (pintype "unspecified"))
    )
    (net (code "85") (name "unconnected-(U10-MQSR{slash}CS-Pad12)") (class "Default")
      (node (ref "U10") (pin "12") (pinfunction "MQSR/CS_12") (pintype "unspecified"))
    )
    (net (code "86") (name "unconnected-(U10-OUT1B-Pad24)") (class "Default")
      (node (ref "U10") (pin "24") (pinfunction "OUT1B_24") (pintype "unspecified"))
    )
    (net (code "87") (name "unconnected-(U10-OUT1C-Pad11)") (class "Default")
      (node (ref "U10") (pin "11") (pinfunction "OUT1C_11") (pintype "unspecified"))
    )
    (net (code "88") (name "unconnected-(U10-SCK-Pad35)") (class "Default")
      (node (ref "U10") (pin "35") (pinfunction "SCK_35") (pintype "unspecified"))
    )
    (net (code "89") (name "unconnected-(U10-SCL2{slash}TX6{slash}A10-Pad16)") (class "Default")
      (node (ref "U10") (pin "16") (pinfunction "SCL2/TX6/A10_16") (pintype "unspecified"))
    )
    (net (code "90") (name "unconnected-(U10-TX4{slash}A3-Pad39)") (class "Default")
      (node (ref "U10") (pin "39") (pinfunction "TX4/A3_39") (pintype "unspecified"))
    )
    (net (code "91") (name "unconnected-(U12-1IN-Pad1)") (class "Default")
      (node (ref "U12") (pin "1") (pinfunction "1IN_1") (pintype "unspecified"))
    )
    (net (code "92") (name "unconnected-(U12-1OUT-Pad18)") (class "Default")
      (node (ref "U12") (pin "18") (pinfunction "1OUT_18") (pintype "unspecified"))
    )
    (net (code "93") (name "unconnected-(U12-2IN-Pad2)") (class "Default")
      (node (ref "U12") (pin "2") (pinfunction "2IN_2") (pintype "unspecified"))
    )
    (net (code "94") (name "unconnected-(U12-2OUT-Pad17)") (class "Default")
      (node (ref "U12") (pin "17") (pinfunction "2OUT_17") (pintype "unspecified"))
    )
    (net (code "95") (name "unconnected-(U12-8IN-Pad8)") (class "Default")
      (node (ref "U12") (pin "8") (pinfunction "8IN_8") (pintype "unspecified"))
    )
    (net (code "96") (name "unconnected-(U12-8OUT-Pad11)") (class "Default")
      (node (ref "U12") (pin "11") (pinfunction "8OUT_11") (pintype "unspecified"))
    )
    (net (code "97") (name "unconnected-(U12-COMMON-Pad10)") (class "Default")
      (node (ref "U12") (pin "10") (pinfunction "COMMON_10") (pintype "unspecified"))
    )
  )
)
